# RS232_MAX3232.net
KiCad netlist of a schematic drawn in Altium Designer
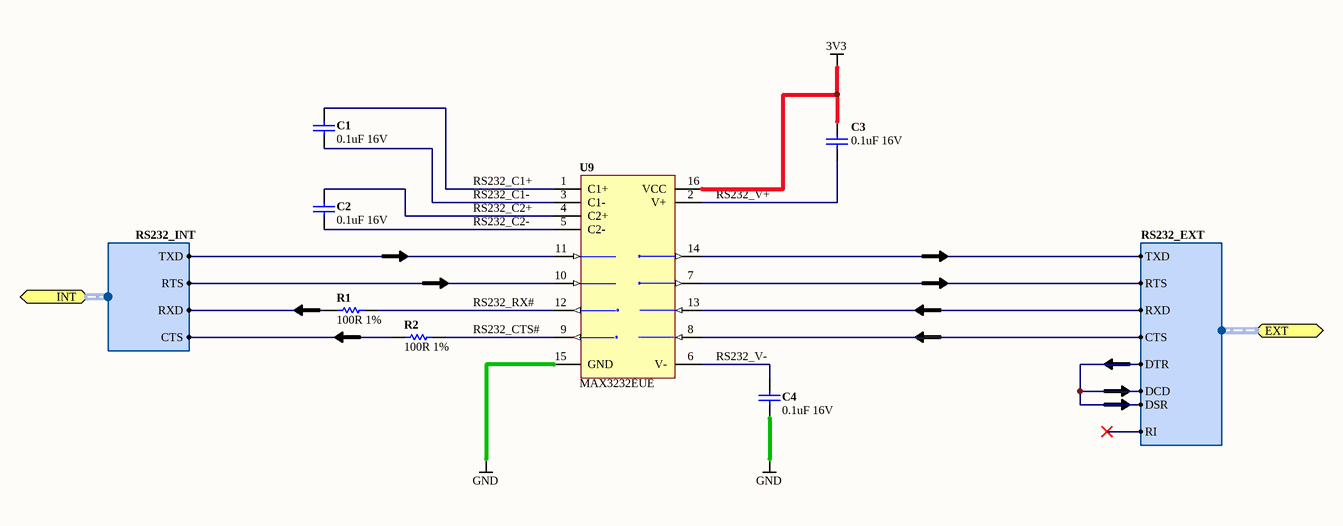
[diagram p0: RS232_MAX3232.SchDoc]

(export (version "E")
  (design (tool "Eeschema 10.0.6"))
  (components
    (comp (ref "C1")
      (value "0.1uF 16V")
      (footprint "CAPC1005-STAR")
      (description "Capacitor, Ceramic, 0.1uF 10% 16V 0402 (1005) X7R")
      (fields (field (name "TOLERANCE") "10 %"))
      (libsource (lib "altium-import") (part "root_0_CAP-NP_"))
    )
    (comp (ref "C2")
      (value "0.1uF 16V")
      (footprint "CAPC1005-STAR")
      (description "Capacitor, Ceramic, 0.1uF 10% 16V 0402 (1005) X7R")
      (fields (field (name "TOLERANCE") "10 %"))
      (libsource (lib "altium-import") (part "root_0_CAP-NP_"))
    )
    (comp (ref "C3")
      (value "0.1uF 16V")
      (footprint "CAPC1005-STAR")
      (description "Capacitor, Ceramic, 0.1uF 10% 16V 0402 (1005) X7R")
      (fields (field (name "TOLERANCE") "10 %"))
      (libsource (lib "altium-import") (part "root_0_CAP-NP_"))
    )
    (comp (ref "C4")
      (value "0.1uF 16V")
      (footprint "CAPC1005-STAR")
      (description "Capacitor, Ceramic, 0.1uF 10% 16V 0402 (1005) X7R")
      (fields (field (name "TOLERANCE") "10 %"))
      (libsource (lib "altium-import") (part "root_0_CAP-NP_"))
    )
    (comp (ref "R1")
      (value "100R 1%")
      (footprint "RESC1005-STAR")
      (description "Resistor, 100R 1% 0402 (1005)")
      (fields (field (name "TOLERANCE") "1 %"))
      (libsource (lib "altium-import") (part "root_1_RES_"))
    )
    (comp (ref "R2")
      (value "100R 1%")
      (footprint "RESC1005-STAR")
      (description "Resistor, 100R 1% 0402 (1005)")
      (fields (field (name "TOLERANCE") "1 %"))
      (libsource (lib "altium-import") (part "root_1_RES_"))
    )
    (comp (ref "U9")
      (value "MAX3232EUE")
      (footprint "TSOP65P638-16")
      (libsource (lib "altium-import") (part "root_0_MAX3232_"))
    )
  )
  (nets
    (net (code "3") (name "/RS232_C1+") (class "Default")
      (node (ref "C1") (pin "1") (pinfunction "1_1") (pintype "passive"))
      (node (ref "U9") (pin "1") (pinfunction "C1+_1") (pintype "passive"))
    )
    (net (code "4") (name "/RS232_C1-") (class "Default")
      (node (ref "C1") (pin "2") (pinfunction "2_2") (pintype "passive"))
      (node (ref "U9") (pin "3") (pinfunction "C1-_3") (pintype "passive"))
    )
    (net (code "5") (name "/RS232_C2+") (class "Default")
      (node (ref "C2") (pin "1") (pinfunction "1_1") (pintype "passive"))
      (node (ref "U9") (pin "4") (pinfunction "C2+_4") (pintype "passive"))
    )
    (net (code "6") (name "/RS232_C2-") (class "Default")
      (node (ref "C2") (pin "2") (pinfunction "2_2") (pintype "passive"))
      (node (ref "U9") (pin "5") (pinfunction "C2-_5") (pintype "passive"))
    )
    (net (code "7") (name "/RS232_CTS#") (class "Default")
      (node (ref "R2") (pin "2") (pinfunction "2_2") (pintype "passive"))
      (node (ref "U9") (pin "9") (pinfunction "R2OUT_9") (pintype "output"))
    )
    (net (code "8") (name "/RS232_RX#") (class "Default")
      (node (ref "R1") (pin "2") (pinfunction "2_2") (pintype "passive"))
      (node (ref "U9") (pin "12") (pinfunction "R1OUT_12") (pintype "output"))
    )
    (net (code "9") (name "/RS232_V+") (class "Default")
      (node (ref "C3") (pin "2") (pinfunction "2_2") (pintype "passive"))
      (node (ref "U9") (pin "2") (pinfunction "V+_2") (pintype "power_in"))
    )
    (net (code "10") (name "/RS232_V-") (class "Default")
      (node (ref "C4") (pin "1") (pinfunction "1_1") (pintype "passive"))
      (node (ref "U9") (pin "6") (pinfunction "V-_6") (pintype "power_in"))
    )
    (net (code "13") (name "3V3") (class "Default")
      (node (ref "C3") (pin "1") (pinfunction "1_1") (pintype "passive"))
      (node (ref "U9") (pin "16") (pinfunction "VCC_16") (pintype "power_in"))
    )
    (net (code "14") (name "GND") (class "Default")
      (node (ref "C4") (pin "2") (pinfunction "2_2") (pintype "passive"))
      (node (ref "U9") (pin "15") (pinfunction "GND_15") (pintype "power_in"))
    )
    (net (code "15") (name "unconnected-(R1-Pad1)") (class "Default")
      (node (ref "R1") (pin "1") (pinfunction "1_1") (pintype "passive"))
    )
    (net (code "16") (name "unconnected-(R2-Pad1)") (class "Default")
      (node (ref "R2") (pin "1") (pinfunction "1_1") (pintype "passive"))
    )
    (net (code "17") (name "unconnected-(U9-R1IN-Pad13)") (class "Default")
      (node (ref "U9") (pin "13") (pinfunction "R1IN_13") (pintype "input"))
    )
    (net (code "18") (name "unconnected-(U9-R2IN-Pad8)") (class "Default")
      (node (ref "U9") (pin "8") (pinfunction "R2IN_8") (pintype "input"))
    )
    (net (code "19") (name "unconnected-(U9-T1IN-Pad11)") (class "Default")
      (node (ref "U9") (pin "11") (pinfunction "T1IN_11") (pintype "input"))
    )
    (net (code "20") (name "unconnected-(U9-T1OUT-Pad14)") (class "Default")
      (node (ref "U9") (pin "14") (pinfunction "T1OUT_14") (pintype "output"))
    )
    (net (code "21") (name "unconnected-(U9-T2IN-Pad10)") (class "Default")
      (node (ref "U9") (pin "10") (pinfunction "T2IN_10") (pintype "input"))
    )
    (net (code "22") (name "unconnected-(U9-T2OUT-Pad7)") (class "Default")
      (node (ref "U9") (pin "7") (pinfunction "T2OUT_7") (pintype "output"))
    )
  )
)
